# tm8.net
KiCad netlist of a schematic drawn in EAGLE
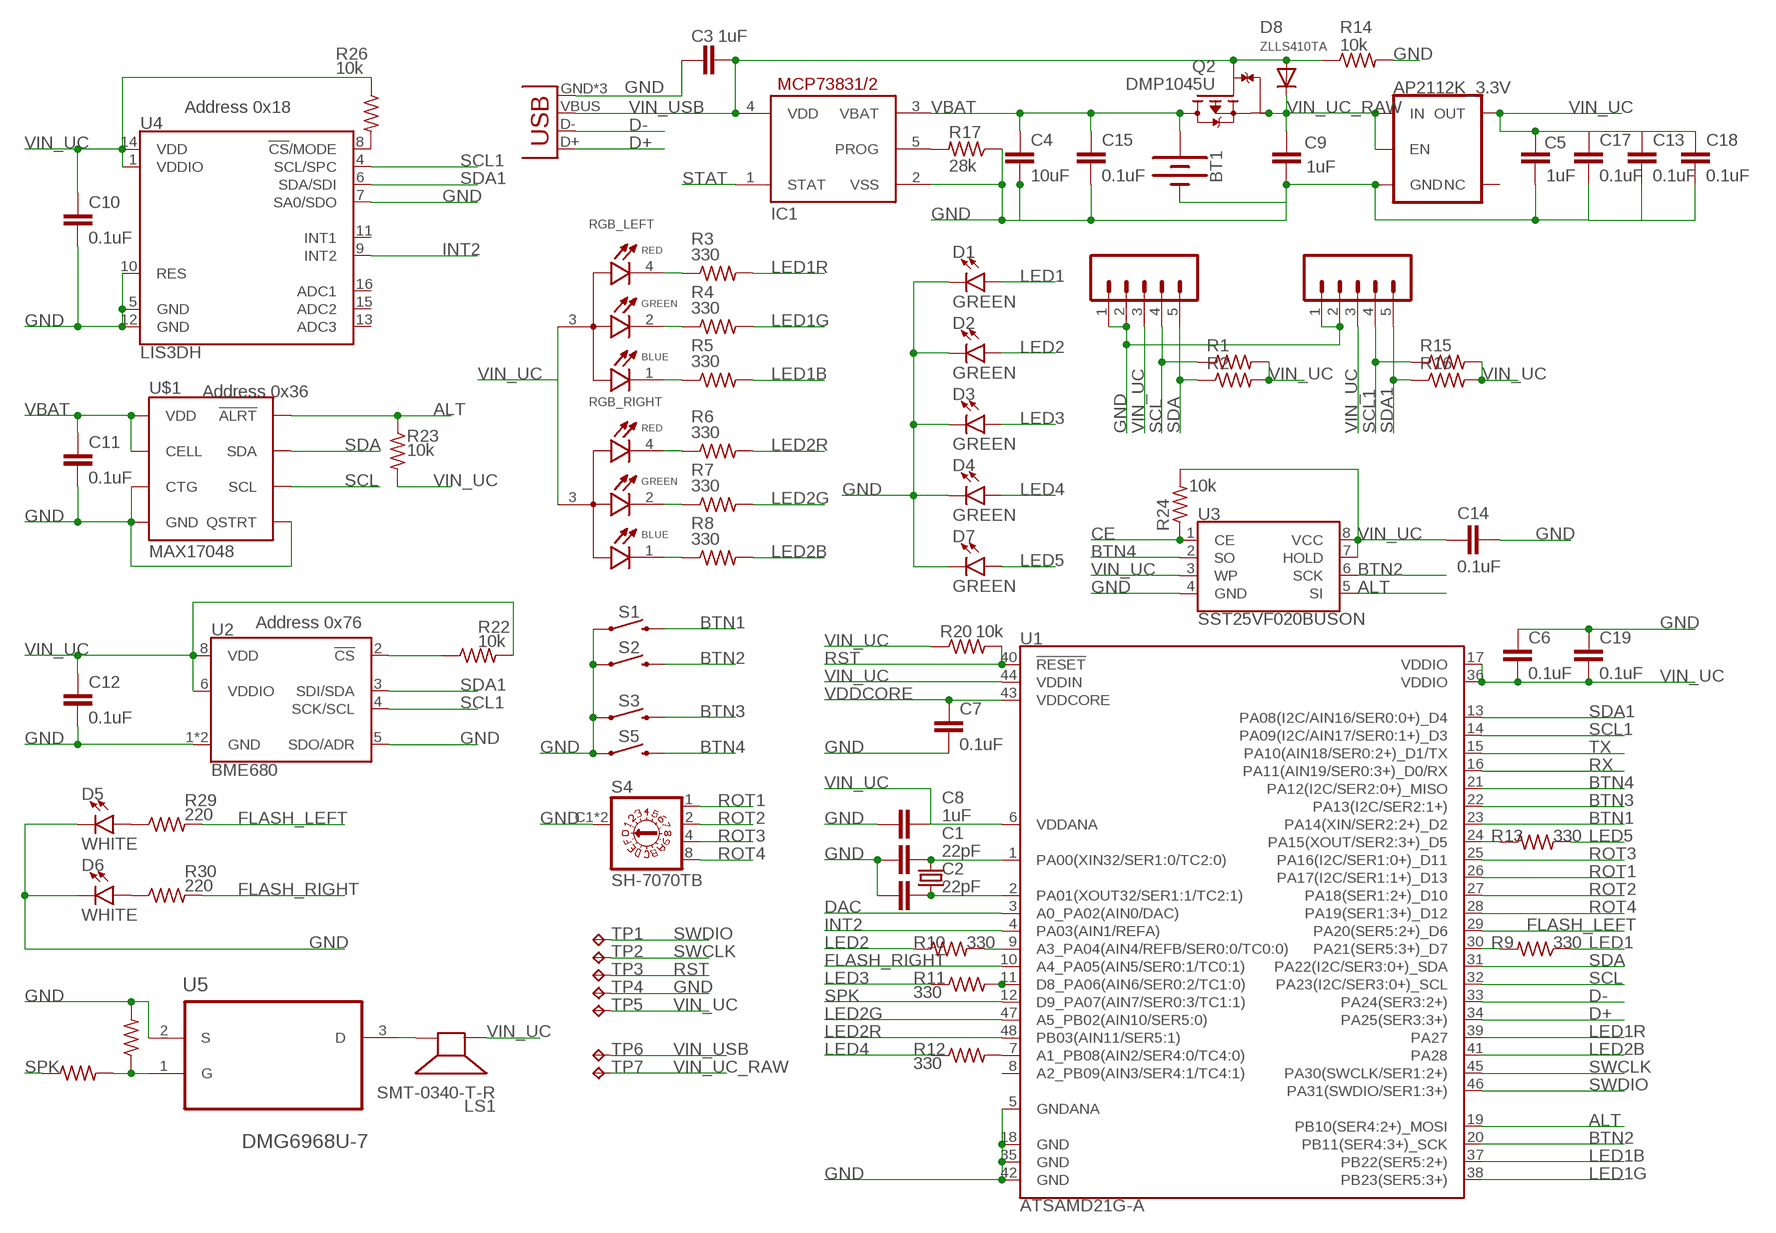
[diagram p0: schematic, sheet 1]

(export (version "E")
  (design (tool "Eeschema 10.0.6"))
  (components
    (comp (ref "AP2112K_3.3V")
      (value "3.3V")
      (footprint "eagle-import:SOT23-5")
      (libsource (lib "eagle-import") (part "V_REG_AP2112K-3.3V"))
    )
    (comp (ref "BT1")
      (value "BATTERY-20MM_SMD_4LEGS_OVERPASTE_INNER")
      (footprint "eagle-import:BATTCON_20MM_4LEGS_OVERPASTE_INNER")
      (libsource (lib "eagle-import") (part "BATTERY-20MM_SMD_4LEGS_OVERPASTE_INNER"))
    )
    (comp (ref "C1")
      (value "22pF")
      (footprint "eagle-import:C0402")
      (libsource (lib "eagle-import") (part "C-EUC0402"))
    )
    (comp (ref "C2")
      (value "22pF")
      (footprint "eagle-import:C0402")
      (libsource (lib "eagle-import") (part "C-EUC0402"))
    )
    (comp (ref "C3")
      (value "1uF")
      (footprint "eagle-import:C0402")
      (libsource (lib "eagle-import") (part "C-EUC0402"))
    )
    (comp (ref "C4")
      (value "10uF")
      (footprint "eagle-import:C0402")
      (libsource (lib "eagle-import") (part "C-EUC0402"))
    )
    (comp (ref "C5")
      (value "1uF")
      (footprint "eagle-import:C0402")
      (libsource (lib "eagle-import") (part "C-EUC0402"))
    )
    (comp (ref "C6")
      (value "0.1uF")
      (footprint "eagle-import:C0402")
      (libsource (lib "eagle-import") (part "C-EUC0402"))
    )
    (comp (ref "C7")
      (value "0.1uF")
      (footprint "eagle-import:C0402")
      (libsource (lib "eagle-import") (part "C-EUC0402"))
    )
    (comp (ref "C8")
      (value "1uF")
      (footprint "eagle-import:C0402")
      (libsource (lib "eagle-import") (part "C-EUC0402"))
    )
    (comp (ref "C9")
      (value "1uF")
      (footprint "eagle-import:C0402")
      (libsource (lib "eagle-import") (part "C-EUC0402"))
    )
    (comp (ref "C10")
      (value "0.1uF")
      (footprint "eagle-import:C0402")
      (libsource (lib "eagle-import") (part "C-EUC0402"))
    )
    (comp (ref "C11")
      (value "0.1uF")
      (footprint "eagle-import:C0402")
      (libsource (lib "eagle-import") (part "C-EUC0402"))
    )
    (comp (ref "C12")
      (value "0.1uF")
      (footprint "eagle-import:C0402")
      (libsource (lib "eagle-import") (part "C-EUC0402"))
    )
    (comp (ref "C13")
      (value "0.1uF")
      (footprint "eagle-import:C0402")
      (libsource (lib "eagle-import") (part "C-EUC0402"))
    )
    (comp (ref "C14")
      (value "0.1uF")
      (footprint "eagle-import:C0402")
      (libsource (lib "eagle-import") (part "C-EUC0402"))
    )
    (comp (ref "C15")
      (value "0.1uF")
      (footprint "eagle-import:C0402")
      (libsource (lib "eagle-import") (part "C-EUC0402"))
    )
    (comp (ref "C17")
      (value "0.1uF")
      (footprint "eagle-import:C0402")
      (libsource (lib "eagle-import") (part "C-EUC0402"))
    )
    (comp (ref "C18")
      (value "0.1uF")
      (footprint "eagle-import:C0402")
      (libsource (lib "eagle-import") (part "C-EUC0402"))
    )
    (comp (ref "C19")
      (value "0.1uF")
      (footprint "eagle-import:C0402")
      (libsource (lib "eagle-import") (part "C-EUC0402"))
    )
    (comp (ref "D1")
      (value "GREEN")
      (footprint "eagle-import:LED-1206")
      (libsource (lib "eagle-import") (part "LED-GREEN1206"))
    )
    (comp (ref "D2")
      (value "GREEN")
      (footprint "eagle-import:LED-1206")
      (libsource (lib "eagle-import") (part "LED-GREEN1206"))
    )
    (comp (ref "D3")
      (value "GREEN")
      (footprint "eagle-import:LED-1206")
      (libsource (lib "eagle-import") (part "LED-GREEN1206"))
    )
    (comp (ref "D4")
      (value "GREEN")
      (footprint "eagle-import:LED-1206")
      (libsource (lib "eagle-import") (part "LED-GREEN1206"))
    )
    (comp (ref "D5")
      (value "WHITE")
      (footprint "eagle-import:LED-1206")
      (libsource (lib "eagle-import") (part "LED-WHITE1206"))
    )
    (comp (ref "D6")
      (value "WHITE")
      (footprint "eagle-import:LED-1206")
      (libsource (lib "eagle-import") (part "LED-WHITE1206"))
    )
    (comp (ref "D7")
      (value "GREEN")
      (footprint "eagle-import:LED-1206")
      (libsource (lib "eagle-import") (part "LED-GREEN1206"))
    )
    (comp (ref "D8")
      (value "ZLLS410TA")
      (footprint "eagle-import:SOD-323F")
      (libsource (lib "eagle-import") (part "DIODESOD-323F"))
    )
    (comp (ref "IC1")
      (value "MCP73831/OT")
      (footprint "eagle-import:SOT23-5L")
      (libsource (lib "eagle-import") (part "MCP73831/OT"))
    )
    (comp (ref "JP2")
      (value "USB-MICROB")
      (footprint "eagle-import:USB-MICROB")
      (libsource (lib "eagle-import") (part "USB-MICROB"))
    )
    (comp (ref "LCD1")
      (value "CONN_05VERT_FEMALE_HEADER")
      (footprint "eagle-import:1X05_SMD_VERTICAL_COMBO")
      (libsource (lib "eagle-import") (part "CONN_05VERT_FEMALE_HEADER"))
    )
    (comp (ref "LCD2")
      (value "CONN_05VERT_FEMALE_HEADER")
      (footprint "eagle-import:1X05_SMD_VERTICAL_COMBO")
      (libsource (lib "eagle-import") (part "CONN_05VERT_FEMALE_HEADER"))
    )
    (comp (ref "LS1")
      (value "SMT-0340-T-R")
      (footprint "eagle-import:XDCR_SMT-0340-T-R")
      (fields (field (name "MANUFACTURER") "Pui Audio"))
      (libsource (lib "eagle-import") (part "SMT-0340-T-R"))
    )
    (comp (ref "Q2")
      (value "DMP1045U")
      (footprint "eagle-import:SOT91P240X110-3N")
      (fields (field (name "MF") "Diodes Inc."))
      (libsource (lib "eagle-import") (part "DMP1045U"))
    )
    (comp (ref "R1")
      (value "R-US_R0402")
      (footprint "eagle-import:R0402")
      (libsource (lib "eagle-import") (part "adafruit_25768682_R-US_R0402"))
    )
    (comp (ref "R2")
      (value "R-US_R0402")
      (footprint "eagle-import:R0402")
      (libsource (lib "eagle-import") (part "adafruit_25768682_R-US_R0402"))
    )
    (comp (ref "R3")
      (value "330")
      (footprint "eagle-import:R0402")
      (libsource (lib "eagle-import") (part "rcl_334_R-US_R0402"))
    )
    (comp (ref "R4")
      (value "330")
      (footprint "eagle-import:R0402")
      (libsource (lib "eagle-import") (part "rcl_334_R-US_R0402"))
    )
    (comp (ref "R5")
      (value "330")
      (footprint "eagle-import:R0402")
      (libsource (lib "eagle-import") (part "rcl_334_R-US_R0402"))
    )
    (comp (ref "R6")
      (value "330")
      (footprint "eagle-import:R0402")
      (libsource (lib "eagle-import") (part "rcl_334_R-US_R0402"))
    )
    (comp (ref "R7")
      (value "330")
      (footprint "eagle-import:R0402")
      (libsource (lib "eagle-import") (part "rcl_334_R-US_R0402"))
    )
    (comp (ref "R8")
      (value "330")
      (footprint "eagle-import:R0402")
      (libsource (lib "eagle-import") (part "rcl_334_R-US_R0402"))
    )
    (comp (ref "R9")
      (value "330")
      (footprint "eagle-import:R0402")
      (libsource (lib "eagle-import") (part "rcl_334_R-US_R0402"))
    )
    (comp (ref "R10")
      (value "330")
      (footprint "eagle-import:R0402")
      (libsource (lib "eagle-import") (part "rcl_334_R-US_R0402"))
    )
    (comp (ref "R11")
      (value "330")
      (footprint "eagle-import:R0402")
      (libsource (lib "eagle-import") (part "rcl_334_R-US_R0402"))
    )
    (comp (ref "R12")
      (value "330")
      (footprint "eagle-import:R0402")
      (libsource (lib "eagle-import") (part "rcl_334_R-US_R0402"))
    )
    (comp (ref "R13")
      (value "330")
      (footprint "eagle-import:R0402")
      (libsource (lib "eagle-import") (part "rcl_334_R-US_R0402"))
    )
    (comp (ref "R14")
      (value "10k")
      (footprint "eagle-import:R0402")
      (libsource (lib "eagle-import") (part "R-US_R0402"))
    )
    (comp (ref "R15")
      (value "R-US_R0402")
      (footprint "eagle-import:R0402")
      (libsource (lib "eagle-import") (part "adafruit_25768682_R-US_R0402"))
    )
    (comp (ref "R16")
      (value "R-US_R0402")
      (footprint "eagle-import:R0402")
      (libsource (lib "eagle-import") (part "adafruit_25768682_R-US_R0402"))
    )
    (comp (ref "R17")
      (value "28k")
      (footprint "eagle-import:R0402")
      (libsource (lib "eagle-import") (part "adafruit_25768682_R-US_R0402"))
    )
    (comp (ref "R18")
      (value "220")
      (footprint "eagle-import:R0402")
      (libsource (lib "eagle-import") (part "rcl_334_R-US_R0402"))
    )
    (comp (ref "R19")
      (value "220")
      (footprint "eagle-import:R0402")
      (libsource (lib "eagle-import") (part "rcl_334_R-US_R0402"))
    )
    (comp (ref "R20")
      (value "10k")
      (footprint "eagle-import:R0402")
      (libsource (lib "eagle-import") (part "adafruit_25768682_R-US_R0402"))
    )
    (comp (ref "R22")
      (value "10k")
      (footprint "eagle-import:R0402")
      (libsource (lib "eagle-import") (part "rcl_334_R-US_R0402"))
    )
    (comp (ref "R23")
      (value "10k")
      (footprint "eagle-import:R0402")
      (libsource (lib "eagle-import") (part "rcl_334_R-US_R0402"))
    )
    (comp (ref "R24")
      (value "10k")
      (footprint "eagle-import:R0402")
      (libsource (lib "eagle-import") (part "rcl_334_R-US_R0402"))
    )
    (comp (ref "R26")
      (value "10k")
      (footprint "eagle-import:R0402")
      (libsource (lib "eagle-import") (part "rcl_334_R-US_R0402"))
    )
    (comp (ref "R29")
      (value "220")
      (footprint "eagle-import:R0402")
      (libsource (lib "eagle-import") (part "rcl_334_R-US_R0402"))
    )
    (comp (ref "R30")
      (value "220")
      (footprint "eagle-import:R0402")
      (libsource (lib "eagle-import") (part "rcl_334_R-US_R0402"))
    )
    (comp (ref "RGB_LEFT")
      (value "EAST1616RGBA3")
      (footprint "eagle-import:LED_EAST1616RGBA3")
      (fields (field (name "MF") "Everlight Electronics"))
      (libsource (lib "eagle-import") (part "EAST1616RGBA3"))
    )
    (comp (ref "RGB_RIGHT")
      (value "EAST1616RGBA3")
      (footprint "eagle-import:LED_EAST1616RGBA3")
      (fields (field (name "MF") "Everlight Electronics"))
      (libsource (lib "eagle-import") (part "EAST1616RGBA3"))
    )
    (comp (ref "S1")
      (value "MOMENTARY-SWITCH-SPST-SMD-6.0X3.5MM")
      (footprint "eagle-import:TACTILE_SWITCH_SMD_6.0X3.5MM")
      (libsource (lib "eagle-import") (part "MOMENTARY-SWITCH-SPST-SMD-6.0X3.5MM"))
    )
    (comp (ref "S2")
      (value "MOMENTARY-SWITCH-SPST-SMD-6.0X3.5MM")
      (footprint "eagle-import:TACTILE_SWITCH_SMD_6.0X3.5MM")
      (libsource (lib "eagle-import") (part "MOMENTARY-SWITCH-SPST-SMD-6.0X3.5MM"))
    )
    (comp (ref "S3")
      (value "MOMENTARY-SWITCH-SPST-SMD-6.0X3.5MM")
      (footprint "eagle-import:TACTILE_SWITCH_SMD_6.0X3.5MM")
      (libsource (lib "eagle-import") (part "MOMENTARY-SWITCH-SPST-SMD-6.0X3.5MM"))
    )
    (comp (ref "S4")
      (value "SH-7070TB")
      (footprint "eagle-import:SH-7070B")
      (fields (field (name "MF") "Nidec Copal"))
      (libsource (lib "eagle-import") (part "SH-7070TB"))
    )
    (comp (ref "S5")
      (value "MOMENTARY-SWITCH-SPST-SMD-6.0X3.5MM")
      (footprint "eagle-import:TACTILE_SWITCH_SMD_6.0X3.5MM")
      (libsource (lib "eagle-import") (part "MOMENTARY-SWITCH-SPST-SMD-6.0X3.5MM"))
    )
    (comp (ref "TP1")
      (value "TPTP14R")
      (footprint "eagle-import:TP14R")
      (libsource (lib "eagle-import") (part "TPTP14R"))
    )
    (comp (ref "TP2")
      (value "TPTP14R")
      (footprint "eagle-import:TP14R")
      (libsource (lib "eagle-import") (part "TPTP14R"))
    )
    (comp (ref "TP3")
      (value "TPTP14R")
      (footprint "eagle-import:TP14R")
      (libsource (lib "eagle-import") (part "TPTP14R"))
    )
    (comp (ref "TP4")
      (value "TPTP14R")
      (footprint "eagle-import:TP14R")
      (libsource (lib "eagle-import") (part "TPTP14R"))
    )
    (comp (ref "TP5")
      (value "TPTP14R")
      (footprint "eagle-import:TP14R")
      (libsource (lib "eagle-import") (part "TPTP14R"))
    )
    (comp (ref "TP6")
      (value "TPTP14R")
      (footprint "eagle-import:TP14R")
      (libsource (lib "eagle-import") (part "TPTP14R"))
    )
    (comp (ref "TP7")
      (value "TPTP14R")
      (footprint "eagle-import:TP14R")
      (libsource (lib "eagle-import") (part "TPTP14R"))
    )
    (comp (ref "U$1")
      (value "MAX17048")
      (footprint "eagle-import:DFN-8")
      (libsource (lib "eagle-import") (part "MAX17048DFN8"))
    )
    (comp (ref "U1")
      (value "ATSAMD21G-A")
      (footprint "eagle-import:TQFP-48")
      (libsource (lib "eagle-import") (part "ATSAMD21G-A"))
    )
    (comp (ref "U2")
      (value "BME680")
      (footprint "eagle-import:LGA3.0X3.0")
      (libsource (lib "eagle-import") (part "BME680-LGA"))
    )
    (comp (ref "U3")
      (value "SST25VF020BUSON")
      (footprint "eagle-import:USON_3X2MM")
      (fields
        (field (name "DIGIKEY_PART") "SST25VF020B-80-4I-Q3AE-TCT-ND")
        (field (name "MANU_PART") "SST25VF020B-80-4I-Q3AE-T")
      )
      (libsource (lib "eagle-import") (part "SST25VF020BUSON"))
    )
    (comp (ref "U4")
      (value "LIS3DH")
      (footprint "eagle-import:LGA-16-3X3")
      (libsource (lib "eagle-import") (part "LIS3DH"))
    )
    (comp (ref "U5")
      (value "DMG6968U-7")
      (footprint "eagle-import:SOT95P240X110-3N")
      (fields (field (name "MF") "Diodes Inc."))
      (libsource (lib "eagle-import") (part "DMG6968U-7"))
    )
    (comp (ref "Y1")
      (value "32.768kHz")
      (footprint "eagle-import:CRYSTAL-SMD-3.2X1.5MM")
      (libsource (lib "eagle-import") (part "CRYSTAL-32.768KHZSMD-3.2X1.5"))
    )
  )
  (nets
    (net (code "1") (name "/ALT") (class "Default")
      (node (ref "R23") (pin "1") (pinfunction "1_1") (pintype "passive"))
      (node (ref "U$1") (pin "P$5") (pinfunction "~{ALRT}_P$5") (pintype "bidirectional"))
      (node (ref "U1") (pin "19") (pinfunction "PB10(SER4:2+)_MOSI_19") (pintype "bidirectional"))
      (node (ref "U3") (pin "5") (pinfunction "SI_5") (pintype "bidirectional"))
    )
    (net (code "2") (name "/BTN1") (class "Default")
      (node (ref "S1") (pin "2") (pinfunction "2_2") (pintype "passive"))
      (node (ref "U1") (pin "23") (pinfunction "PA14(XIN/SER2:2+)_D2_23") (pintype "bidirectional"))
    )
    (net (code "3") (name "/BTN2") (class "Default")
      (node (ref "S2") (pin "2") (pinfunction "2_2") (pintype "passive"))
      (node (ref "U1") (pin "20") (pinfunction "PB11(SER4:3+)_SCK_20") (pintype "bidirectional"))
      (node (ref "U3") (pin "6") (pinfunction "SCK_6") (pintype "bidirectional"))
    )
    (net (code "4") (name "/BTN3") (class "Default")
      (node (ref "S3") (pin "2") (pinfunction "2_2") (pintype "passive"))
      (node (ref "U1") (pin "22") (pinfunction "PA13(I2C/SER2:1+)_22") (pintype "bidirectional"))
    )
    (net (code "5") (name "/BTN4") (class "Default")
      (node (ref "S5") (pin "2") (pinfunction "2_2") (pintype "passive"))
      (node (ref "U1") (pin "21") (pinfunction "PA12(I2C/SER2:0+)_MISO_21") (pintype "bidirectional"))
      (node (ref "U3") (pin "2") (pinfunction "SO_2") (pintype "bidirectional"))
    )
    (net (code "6") (name "/CE") (class "Default")
      (node (ref "R24") (pin "1") (pinfunction "1_1") (pintype "passive"))
      (node (ref "U3") (pin "1") (pinfunction "CE_1") (pintype "bidirectional"))
    )
    (net (code "7") (name "/D+") (class "Default")
      (node (ref "JP2") (pin "D+") (pinfunction "D+_D+") (pintype "bidirectional"))
      (node (ref "U1") (pin "34") (pinfunction "PA25(SER3:3+)_34") (pintype "bidirectional"))
    )
    (net (code "8") (name "/D-") (class "Default")
      (node (ref "JP2") (pin "D-") (pinfunction "D-_D-") (pintype "bidirectional"))
      (node (ref "U1") (pin "33") (pinfunction "PA24(SER3:2+)_33") (pintype "bidirectional"))
    )
    (net (code "9") (name "/DAC") (class "Default")
      (node (ref "U1") (pin "3") (pinfunction "A0_PA02(AIN0/DAC)_3") (pintype "bidirectional"))
    )
    (net (code "10") (name "/FLASH_LEFT") (class "Default")
      (node (ref "R29") (pin "2") (pinfunction "2_2") (pintype "passive"))
      (node (ref "U1") (pin "29") (pinfunction "PA20(SER5:2+)_D6_29") (pintype "bidirectional"))
    )
    (net (code "11") (name "/FLASH_RIGHT") (class "Default")
      (node (ref "R30") (pin "2") (pinfunction "2_2") (pintype "passive"))
      (node (ref "U1") (pin "10") (pinfunction "A4_PA05(AIN5/SER0:1/TC0:1)_10") (pintype "bidirectional"))
    )
    (net (code "12") (name "/GND") (class "Default")
      (node (ref "AP2112K_3.3V") (pin "2") (pinfunction "GND_2") (pintype "input"))
      (node (ref "BT1") (pin "2") (pinfunction "-_2") (pintype "power_in"))
      (node (ref "C1") (pin "1") (pinfunction "1_1") (pintype "passive"))
      (node (ref "C10") (pin "2") (pinfunction "2_2") (pintype "passive"))
      (node (ref "C11") (pin "2") (pinfunction "2_2") (pintype "passive"))
      (node (ref "C12") (pin "2") (pinfunction "2_2") (pintype "passive"))
      (node (ref "C13") (pin "2") (pinfunction "2_2") (pintype "passive"))
      (node (ref "C14") (pin "2") (pinfunction "2_2") (pintype "passive"))
      (node (ref "C15") (pin "2") (pinfunction "2_2") (pintype "passive"))
      (node (ref "C17") (pin "2") (pinfunction "2_2") (pintype "passive"))
      (node (ref "C18") (pin "2") (pinfunction "2_2") (pintype "passive"))
      (node (ref "C19") (pin "1") (pinfunction "1_1") (pintype "passive"))
      (node (ref "C2") (pin "1") (pinfunction "1_1") (pintype "passive"))
      (node (ref "C3") (pin "1") (pinfunction "1_1") (pintype "passive"))
      (node (ref "C4") (pin "2") (pinfunction "2_2") (pintype "passive"))
      (node (ref "C5") (pin "2") (pinfunction "2_2") (pintype "passive"))
      (node (ref "C6") (pin "1") (pinfunction "1_1") (pintype "passive"))
      (node (ref "C7") (pin "2") (pinfunction "2_2") (pintype "passive"))
      (node (ref "C8") (pin "1") (pinfunction "1_1") (pintype "passive"))
      (node (ref "C9") (pin "2") (pinfunction "2_2") (pintype "passive"))
      (node (ref "D1") (pin "C") (pinfunction "C_C") (pintype "passive"))
      (node (ref "D2") (pin "C") (pinfunction "C_C") (pintype "passive"))
      (node (ref "D3") (pin "C") (pinfunction "C_C") (pintype "passive"))
      (node (ref "D4") (pin "C") (pinfunction "C_C") (pintype "passive"))
      (node (ref "D5") (pin "C") (pinfunction "C_C") (pintype "passive"))
      (node (ref "D6") (pin "C") (pinfunction "C_C") (pintype "passive"))
      (node (ref "D7") (pin "C") (pinfunction "C_C") (pintype "passive"))
      (node (ref "IC1") (pin "2") (pinfunction "VSS_2") (pintype "power_in"))
      (node (ref "JP2") (pin "GND") (pinfunction "GND_GND") (pintype "bidirectional"))
      (node (ref "JP2") (pin "MT1") (pinfunction "GND_MT1") (pintype "bidirectional"))
      (node (ref "JP2") (pin "MT2") (pinfunction "GND_MT2") (pintype "bidirectional"))
      (node (ref "LCD1") (pin "1") (pinfunction "1_1") (pintype "passive"))
      (node (ref "LCD1") (pin "2") (pinfunction "2_2") (pintype "passive"))
      (node (ref "LCD2") (pin "1") (pinfunction "1_1") (pintype "passive"))
      (node (ref "LCD2") (pin "2") (pinfunction "2_2") (pintype "passive"))
      (node (ref "R14") (pin "2") (pinfunction "2_2") (pintype "passive"))
      (node (ref "R17") (pin "1") (pinfunction "1_1") (pintype "passive"))
      (node (ref "R19") (pin "2") (pinfunction "2_2") (pintype "passive"))
      (node (ref "S1") (pin "1") (pinfunction "1_1") (pintype "passive"))
      (node (ref "S2") (pin "1") (pinfunction "1_1") (pintype "passive"))
      (node (ref "S3") (pin "1") (pinfunction "1_1") (pintype "passive"))
      (node (ref "S4") (pin "C1") (pinfunction "C_C1") (pintype "passive"))
      (node (ref "S4") (pin "C2") (pinfunction "C_C2") (pintype "passive"))
      (node (ref "S5") (pin "1") (pinfunction "1_1") (pintype "passive"))
      (node (ref "TP4") (pin "TP") (pinfunction "TP_TP") (pintype "input"))
      (node (ref "U$1") (pin "P$1") (pinfunction "CTG_P$1") (pintype "input"))
      (node (ref "U$1") (pin "P$4") (pinfunction "GND_P$4") (pintype "bidirectional"))
      (node (ref "U$1") (pin "P$6") (pinfunction "QSTRT_P$6") (pintype "bidirectional"))
      (node (ref "U$1") (pin "P$9") (pinfunction "GND_P$9") (pintype "bidirectional"))
      (node (ref "U1") (pin "18") (pinfunction "GND_18") (pintype "bidirectional"))
      (node (ref "U1") (pin "35") (pinfunction "GND_35") (pintype "bidirectional"))
      (node (ref "U1") (pin "42") (pinfunction "GND_42") (pintype "bidirectional"))
      (node (ref "U1") (pin "5") (pinfunction "GNDANA_5") (pintype "bidirectional"))
      (node (ref "U2") (pin "1") (pinfunction "GND_1") (pintype "bidirectional"))
      (node (ref "U2") (pin "5") (pinfunction "SDO/ADR_5") (pintype "bidirectional"))
      (node (ref "U2") (pin "7") (pinfunction "GND_7") (pintype "bidirectional"))
      (node (ref "U3") (pin "4") (pinfunction "GND_4") (pintype "power_in"))
      (node (ref "U4") (pin "10") (pinfunction "RES_10") (pintype "bidirectional"))
      (node (ref "U4") (pin "12") (pinfunction "GND_12") (pintype "bidirectional"))
      (node (ref "U4") (pin "5") (pinfunction "GND_5") (pintype "bidirectional"))
      (node (ref "U4") (pin "7") (pinfunction "SA0/SDO_7") (pintype "bidirectional"))
      (node (ref "U5") (pin "2") (pinfunction "S_2") (pintype "passive"))
    )
    (net (code "13") (name "/INT2") (class "Default")
      (node (ref "U1") (pin "4") (pinfunction "PA03(AIN1/REFA)_4") (pintype "bidirectional"))
      (node (ref "U4") (pin "9") (pinfunction "INT2_9") (pintype "bidirectional"))
    )
    (net (code "14") (name "/LED1") (class "Default")
      (node (ref "D1") (pin "A") (pinfunction "A_A") (pintype "passive"))
      (node (ref "R9") (pin "1") (pinfunction "1_1") (pintype "passive"))
    )
    (net (code "15") (name "/LED1B") (class "Default")
      (node (ref "R5") (pin "2") (pinfunction "2_2") (pintype "passive"))
      (node (ref "U1") (pin "37") (pinfunction "PB22(SER5:2+)_37") (pintype "bidirectional"))
    )
    (net (code "16") (name "/LED1G") (class "Default")
      (node (ref "R4") (pin "2") (pinfunction "2_2") (pintype "passive"))
      (node (ref "U1") (pin "38") (pinfunction "PB23(SER5:3+)_38") (pintype "bidirectional"))
    )
    (net (code "17") (name "/LED1R") (class "Default")
      (node (ref "R3") (pin "2") (pinfunction "2_2") (pintype "passive"))
      (node (ref "U1") (pin "39") (pinfunction "PA27_39") (pintype "bidirectional"))
    )
    (net (code "18") (name "/LED2") (class "Default")
      (node (ref "D2") (pin "A") (pinfunction "A_A") (pintype "passive"))
      (node (ref "R10") (pin "1") (pinfunction "1_1") (pintype "passive"))
    )
    (net (code "19") (name "/LED2B") (class "Default")
      (node (ref "R8") (pin "2") (pinfunction "2_2") (pintype "passive"))
      (node (ref "U1") (pin "41") (pinfunction "PA28_41") (pintype "bidirectional"))
    )
    (net (code "20") (name "/LED2G") (class "Default")
      (node (ref "R7") (pin "2") (pinfunction "2_2") (pintype "passive"))
      (node (ref "U1") (pin "47") (pinfunction "A5_PB02(AIN10/SER5:0)_47") (pintype "bidirectional"))
    )
    (net (code "21") (name "/LED2R") (class "Default")
      (node (ref "R6") (pin "2") (pinfunction "2_2") (pintype "passive"))
      (node (ref "U1") (pin "48") (pinfunction "PB03(AIN11/SER5:1)_48") (pintype "bidirectional"))
    )
    (net (code "22") (name "/LED3") (class "Default")
      (node (ref "D3") (pin "A") (pinfunction "A_A") (pintype "passive"))
      (node (ref "R11") (pin "1") (pinfunction "1_1") (pintype "passive"))
    )
    (net (code "23") (name "/LED4") (class "Default")
      (node (ref "D4") (pin "A") (pinfunction "A_A") (pintype "passive"))
      (node (ref "R12") (pin "1") (pinfunction "1_1") (pintype "passive"))
    )
    (net (code "24") (name "/LED5") (class "Default")
      (node (ref "D7") (pin "A") (pinfunction "A_A") (pintype "passive"))
      (node (ref "R13") (pin "2") (pinfunction "2_2") (pintype "passive"))
    )
    (net (code "25") (name "/ROT1") (class "Default")
      (node (ref "S4") (pin "1") (pinfunction "1_1") (pintype "passive"))
      (node (ref "U1") (pin "26") (pinfunction "PA17(I2C/SER1:1+)_D13_26") (pintype "bidirectional"))
    )
    (net (code "26") (name "/ROT2") (class "Default")
      (node (ref "S4") (pin "2") (pinfunction "2_2") (pintype "passive"))
      (node (ref "U1") (pin "27") (pinfunction "PA18(SER1:2+)_D10_27") (pintype "bidirectional"))
    )
    (net (code "27") (name "/ROT3") (class "Default")
      (node (ref "S4") (pin "4") (pinfunction "4_4") (pintype "passive"))
      (node (ref "U1") (pin "25") (pinfunction "PA16(I2C/SER1:0+)_D11_25") (pintype "bidirectional"))
    )
    (net (code "28") (name "/ROT4") (class "Default")
      (node (ref "S4") (pin "8") (pinfunction "8_8") (pintype "passive"))
      (node (ref "U1") (pin "28") (pinfunction "PA19(SER1:3+)_D12_28") (pintype "bidirectional"))
    )
    (net (code "29") (name "/RST") (class "Default")
      (node (ref "R20") (pin "2") (pinfunction "2_2") (pintype "passive"))
      (node (ref "TP3") (pin "TP") (pinfunction "TP_TP") (pintype "input"))
      (node (ref "U1") (pin "40") (pinfunction "~{RESET}_40") (pintype "bidirectional"))
    )
    (net (code "30") (name "/RX") (class "Default")
      (node (ref "U1") (pin "16") (pinfunction "PA11(AIN19/SER0:3+)_D0/RX_16") (pintype "bidirectional"))
    )
    (net (code "31") (name "/SCL") (class "Default")
      (node (ref "LCD1") (pin "4") (pinfunction "4_4") (pintype "passive"))
      (node (ref "R1") (pin "1") (pinfunction "1_1") (pintype "passive"))
      (node (ref "U$1") (pin "P$7") (pinfunction "SCL_P$7") (pintype "output"))
      (node (ref "U1") (pin "32") (pinfunction "PA23(I2C/SER3:0+)_SCL_32") (pintype "bidirectional"))
    )
    (net (code "32") (name "/SCL1") (class "Default")
      (node (ref "LCD2") (pin "4") (pinfunction "4_4") (pintype "passive"))
      (node (ref "R15") (pin "1") (pinfunction "1_1") (pintype "passive"))
      (node (ref "U1") (pin "14") (pinfunction "PA09(I2C/AIN17/SER0:1+)_D3_14") (pintype "bidirectional"))
      (node (ref "U2") (pin "4") (pinfunction "SCK/SCL_4") (pintype "bidirectional"))
      (node (ref "U4") (pin "4") (pinfunction "SCL/SPC_4") (pintype "bidirectional"))
    )
    (net (code "33") (name "/SDA") (class "Default")
      (node (ref "LCD1") (pin "5") (pinfunction "5_5") (pintype "passive"))
      (node (ref "R2") (pin "1") (pinfunction "1_1") (pintype "passive"))
      (node (ref "U$1") (pin "P$8") (pinfunction "SDA_P$8") (pintype "input"))
      (node (ref "U1") (pin "31") (pinfunction "PA22(I2C/SER3:0+)_SDA_31") (pintype "bidirectional"))
    )
    (net (code "34") (name "/SDA1") (class "Default")
      (node (ref "LCD2") (pin "5") (pinfunction "5_5") (pintype "passive"))
      (node (ref "R16") (pin "1") (pinfunction "1_1") (pintype "passive"))
      (node (ref "U1") (pin "13") (pinfunction "PA08(I2C/AIN16/SER0:0+)_D4_13") (pintype "bidirectional"))
      (node (ref "U2") (pin "3") (pinfunction "SDI/SDA_3") (pintype "bidirectional"))
      (node (ref "U4") (pin "6") (pinfunction "SDA/SDI_6") (pintype "bidirectional"))
    )
    (net (code "35") (name "/SPK") (class "Default")
      (node (ref "R18") (pin "1") (pinfunction "1_1") (pintype "passive"))
      (node (ref "U1") (pin "12") (pinfunction "D9_PA07(AIN7/SER0:3/TC1:1)_12") (pintype "bidirectional"))
    )
    (net (code "36") (name "/STAT") (class "Default")
      (node (ref "IC1") (pin "1") (pinfunction "STAT_1") (pintype "output"))
    )
    (net (code "37") (name "/SWCLK") (class "Default")
      (node (ref "TP2") (pin "TP") (pinfunction "TP_TP") (pintype "input"))
      (node (ref "U1") (pin "45") (pinfunction "PA30(SWCLK/SER1:2+)_45") (pintype "bidirectional"))
    )
    (net (code "38") (name "/SWDIO") (class "Default")
      (node (ref "TP1") (pin "TP") (pinfunction "TP_TP") (pintype "input"))
      (node (ref "U1") (pin "46") (pinfunction "PA31(SWDIO/SER1:3+)_46") (pintype "bidirectional"))
    )
    (net (code "39") (name "/TX") (class "Default")
      (node (ref "U1") (pin "15") (pinfunction "PA10(AIN18/SER0:2+)_D1/TX_15") (pintype "bidirectional"))
    )
    (net (code "40") (name "/VBAT") (class "Default")
      (node (ref "BT1") (pin "1") (pinfunction "+_1") (pintype "power_in"))
      (node (ref "C11") (pin "1") (pinfunction "1_1") (pintype "passive"))
      (node (ref "C15") (pin "1") (pinfunction "1_1") (pintype "passive"))
      (node (ref "C4") (pin "1") (pinfunction "1_1") (pintype "passive"))
      (node (ref "IC1") (pin "3") (pinfunction "VBAT_3") (pintype "bidirectional"))
      (node (ref "Q2") (pin "3") (pinfunction "D_3") (pintype "passive"))
      (node (ref "U$1") (pin "P$2") (pinfunction "CELL_P$2") (pintype "input"))
      (node (ref "U$1") (pin "P$3") (pinfunction "VDD_P$3") (pintype "bidirectional"))
    )
    (net (code "41") (name "/VDDCORE") (class "Default")
      (node (ref "C7") (pin "1") (pinfunction "1_1") (pintype "passive"))
      (node (ref "U1") (pin "43") (pinfunction "VDDCORE_43") (pintype "bidirectional"))
    )
    (net (code "42") (name "/VIN_UC") (class "Default")
      (node (ref "AP2112K_3.3V") (pin "5") (pinfunction "OUT_5") (pintype "passive"))
      (node (ref "C10") (pin "1") (pinfunction "1_1") (pintype "passive"))
      (node (ref "C12") (pin "1") (pinfunction "1_1") (pintype "passive"))
      (node (ref "C13") (pin "1") (pinfunction "1_1") (pintype "passive"))
      (node (ref "C14") (pin "1") (pinfunction "1_1") (pintype "passive"))
      (node (ref "C17") (pin "1") (pinfunction "1_1") (pintype "passive"))
      (node (ref "C18") (pin "1") (pinfunction "1_1") (pintype "passive"))
      (node (ref "C19") (pin "2") (pinfunction "2_2") (pintype "passive"))
      (node (ref "C5") (pin "1") (pinfunction "1_1") (pintype "passive"))
      (node (ref "C6") (pin "2") (pinfunction "2_2") (pintype "passive"))
      (node (ref "C8") (pin "2") (pinfunction "2_2") (pintype "passive"))
      (node (ref "LCD1") (pin "3") (pinfunction "3_3") (pintype "passive"))
      (node (ref "LCD2") (pin "3") (pinfunction "3_3") (pintype "passive"))
      (node (ref "LS1") (pin "P") (pinfunction "P_P") (pintype "passive"))
      (node (ref "R1") (pin "2") (pinfunction "2_2") (pintype "passive"))
      (node (ref "R15") (pin "2") (pinfunction "2_2") (pintype "passive"))
      (node (ref "R16") (pin "2") (pinfunction "2_2") (pintype "passive"))
      (node (ref "R2") (pin "2") (pinfunction "2_2") (pintype "passive"))
      (node (ref "R20") (pin "1") (pinfunction "1_1") (pintype "passive"))
      (node (ref "R22") (pin "2") (pinfunction "2_2") (pintype "passive"))
      (node (ref "R23") (pin "2") (pinfunction "2_2") (pintype "passive"))
      (node (ref "R24") (pin "2") (pinfunction "2_2") (pintype "passive"))
      (node (ref "R26") (pin "1") (pinfunction "1_1") (pintype "passive"))
      (node (ref "RGB_LEFT") (pin "3") (pinfunction "A_3") (pintype "passive"))
      (node (ref "RGB_RIGHT") (pin "3") (pinfunction "A_3") (pintype "passive"))
      (node (ref "TP5") (pin "TP") (pinfunction "TP_TP") (pintype "input"))
      (node (ref "U1") (pin "17") (pinfunction "VDDIO_17") (pintype "bidirectional"))
      (node (ref "U1") (pin "36") (pinfunction "VDDIO_36") (pintype "bidirectional"))
      (node (ref "U1") (pin "44") (pinfunction "VDDIN_44") (pintype "bidirectional"))
      (node (ref "U1") (pin "6") (pinfunction "VDDANA_6") (pintype "bidirectional"))
      (node (ref "U2") (pin "6") (pinfunction "VDDIO_6") (pintype "bidirectional"))
      (node (ref "U2") (pin "8") (pinfunction "VDD_8") (pintype "bidirectional"))
      (node (ref "U3") (pin "3") (pinfunction "WP_3") (pintype "bidirectional"))
      (node (ref "U3") (pin "7") (pinfunction "HOLD_7") (pintype "bidirectional"))
      (node (ref "U3") (pin "8") (pinfunction "VCC_8") (pintype "power_in"))
      (node (ref "U4") (pin "1") (pinfunction "VDDIO_1") (pintype "bidirectional"))
      (node (ref "U4") (pin "14") (pinfunction "VDD_14") (pintype "bidirectional"))
    )
    (net (code "43") (name "/VIN_UC_RAW") (class "Default")
      (node (ref "AP2112K_3.3V") (pin "1") (pinfunction "IN_1") (pintype "input"))
      (node (ref "AP2112K_3.3V") (pin "3") (pinfunction "EN_3") (pintype "input"))
      (node (ref "C9") (pin "1") (pinfunction "1_1") (pintype "passive"))
      (node (ref "D8") (pin "C") (pinfunction "C_C") (pintype "passive"))
      (node (ref "Q2") (pin "2") (pinfunction "S_2") (pintype "passive"))
      (node (ref "TP7") (pin "TP") (pinfunction "TP_TP") (pintype "input"))
    )
    (net (code "44") (name "/VIN_USB") (class "Default")
      (node (ref "C3") (pin "2") (pinfunction "2_2") (pintype "passive"))
      (node (ref "D8") (pin "A") (pinfunction "A_A") (pintype "passive"))
      (node (ref "IC1") (pin "4") (pinfunction "VDD_4") (pintype "power_in"))
      (node (ref "JP2") (pin "VBUS") (pinfunction "VBUS_VBUS") (pintype "bidirectional"))
      (node (ref "Q2") (pin "1") (pinfunction "G_1") (pintype "passive"))
      (node (ref "R14") (pin "1") (pinfunction "1_1") (pintype "passive"))
      (node (ref "TP6") (pin "TP") (pinfunction "TP_TP") (pintype "input"))
    )
    (net (code "45") (name "Net-(D5-PadA)") (class "Default")
      (node (ref "D5") (pin "A") (pinfunction "A_A") (pintype "passive"))
      (node (ref "R29") (pin "1") (pinfunction "1_1") (pintype "passive"))
    )
    (net (code "46") (name "Net-(D6-PadA)") (class "Default")
      (node (ref "D6") (pin "A") (pinfunction "A_A") (pintype "passive"))
      (node (ref "R30") (pin "1") (pinfunction "1_1") (pintype "passive"))
    )
    (net (code "47") (name "Net-(IC1-PROG)") (class "Default")
      (node (ref "IC1") (pin "5") (pinfunction "PROG_5") (pintype "input"))
      (node (ref "R17") (pin "2") (pinfunction "2_2") (pintype "passive"))
    )
    (net (code "48") (name "Net-(RGB_LEFT-B_C)") (class "Default")
      (node (ref "R5") (pin "1") (pinfunction "1_1") (pintype "passive"))
      (node (ref "RGB_LEFT") (pin "1") (pinfunction "B_C_1") (pintype "passive"))
    )
    (net (code "49") (name "Net-(RGB_LEFT-G_C)") (class "Default")
      (node (ref "R4") (pin "1") (pinfunction "1_1") (pintype "passive"))
      (node (ref "RGB_LEFT") (pin "2") (pinfunction "G_C_2") (pintype "passive"))
    )
    (net (code "50") (name "Net-(RGB_LEFT-R_C)") (class "Default")
      (node (ref "R3") (pin "1") (pinfunction "1_1") (pintype "passive"))
      (node (ref "RGB_LEFT") (pin "4") (pinfunction "R_C_4") (pintype "passive"))
    )
    (net (code "51") (name "Net-(RGB_RIGHT-B_C)") (class "Default")
      (node (ref "R8") (pin "1") (pinfunction "1_1") (pintype "passive"))
      (node (ref "RGB_RIGHT") (pin "1") (pinfunction "B_C_1") (pintype "passive"))
    )
    (net (code "52") (name "Net-(RGB_RIGHT-G_C)") (class "Default")
      (node (ref "R7") (pin "1") (pinfunction "1_1") (pintype "passive"))
      (node (ref "RGB_RIGHT") (pin "2") (pinfunction "G_C_2") (pintype "passive"))
    )
    (net (code "53") (name "Net-(RGB_RIGHT-R_C)") (class "Default")
      (node (ref "R6") (pin "1") (pinfunction "1_1") (pintype "passive"))
      (node (ref "RGB_RIGHT") (pin "4") (pinfunction "R_C_4") (pintype "passive"))
    )
    (net (code "54") (name "Net-(U1-A1_PB08(AIN2{slash}SER4:0{slash}TC4:0))") (class "Default")
      (node (ref "R12") (pin "2") (pinfunction "2_2") (pintype "passive"))
      (node (ref "U1") (pin "7") (pinfunction "A1_PB08(AIN2/SER4:0/TC4:0)_7") (pintype "bidirectional"))
    )
    (net (code "55") (name "Net-(U1-A3_PA04(AIN4{slash}REFB{slash}SER0:0{slash}TC0:0))") (class "Default")
      (node (ref "R10") (pin "2") (pinfunction "2_2") (pintype "passive"))
      (node (ref "U1") (pin "9") (pinfunction "A3_PA04(AIN4/REFB/SER0:0/TC0:0)_9") (pintype "bidirectional"))
    )
    (net (code "56") (name "Net-(U1-D8_PA06(AIN6{slash}SER0:2{slash}TC1:0))") (class "Default")
      (node (ref "R11") (pin "2") (pinfunction "2_2") (pintype "passive"))
      (node (ref "U1") (pin "11") (pinfunction "D8_PA06(AIN6/SER0:2/TC1:0)_11") (pintype "bidirectional"))
    )
    (net (code "57") (name "Net-(U1-PA00(XIN32{slash}SER1:0{slash}TC2:0))") (class "Default")
      (node (ref "C1") (pin "2") (pinfunction "2_2") (pintype "passive"))
      (node (ref "U1") (pin "1") (pinfunction "PA00(XIN32/SER1:0/TC2:0)_1") (pintype "bidirectional"))
      (node (ref "Y1") (pin "P$2") (pinfunction "2_P$2") (pintype "passive"))
    )
    (net (code "58") (name "Net-(U1-PA01(XOUT32{slash}SER1:1{slash}TC2:1))") (class "Default")
      (node (ref "C2") (pin "2") (pinfunction "2_2") (pintype "passive"))
      (node (ref "U1") (pin "2") (pinfunction "PA01(XOUT32/SER1:1/TC2:1)_2") (pintype "bidirectional"))
      (node (ref "Y1") (pin "P$1") (pinfunction "1_P$1") (pintype "passive"))
    )
    (net (code "59") (name "Net-(U1-PA15(XOUT{slash}SER2:3+)_D5)") (class "Default")
      (node (ref "R13") (pin "1") (pinfunction "1_1") (pintype "passive"))
      (node (ref "U1") (pin "24") (pinfunction "PA15(XOUT/SER2:3+)_D5_24") (pintype "bidirectional"))
    )
    (net (code "60") (name "Net-(U1-PA21(SER5:3+)_D7)") (class "Default")
      (node (ref "R9") (pin "2") (pinfunction "2_2") (pintype "passive"))
      (node (ref "U1") (pin "30") (pinfunction "PA21(SER5:3+)_D7_30") (pintype "bidirectional"))
    )
    (net (code "61") (name "Net-(U2-~{CS})") (class "Default")
      (node (ref "R22") (pin "1") (pinfunction "1_1") (pintype "passive"))
      (node (ref "U2") (pin "2") (pinfunction "~{CS}_2") (pintype "bidirectional"))
    )
    (net (code "62") (name "Net-(U4-~{CS}{slash}MODE)") (class "Default")
      (node (ref "R26") (pin "2") (pinfunction "2_2") (pintype "passive"))
      (node (ref "U4") (pin "8") (pinfunction "~{CS}/MODE_8") (pintype "bidirectional"))
    )
    (net (code "63") (name "Net-(U5-D)") (class "Default")
      (node (ref "LS1") (pin "N") (pinfunction "N_N") (pintype "passive"))
      (node (ref "U5") (pin "3") (pinfunction "D_3") (pintype "output"))
    )
    (net (code "64") (name "Net-(U5-G)") (class "Default")
      (node (ref "R18") (pin "2") (pinfunction "2_2") (pintype "passive"))
      (node (ref "R19") (pin "1") (pinfunction "1_1") (pintype "passive"))
      (node (ref "U5") (pin "1") (pinfunction "G_1") (pintype "power_in"))
    )
    (net (code "65") (name "unconnected-(AP2112K_3.3V-NC-Pad4)") (class "Default")
      (node (ref "AP2112K_3.3V") (pin "4") (pinfunction "NC_4") (pintype "no_connect"))
    )
    (net (code "66") (name "unconnected-(U1-A2_PB09(AIN3{slash}SER4:1{slash}TC4:1)-Pad8)") (class "Default")
      (node (ref "U1") (pin "8") (pinfunction "A2_PB09(AIN3/SER4:1/TC4:1)_8") (pintype "bidirectional"))
    )
    (net (code "67") (name "unconnected-(U4-ADC1-Pad16)") (class "Default")
      (node (ref "U4") (pin "16") (pinfunction "ADC1_16") (pintype "bidirectional"))
    )
    (net (code "68") (name "unconnected-(U4-ADC2-Pad15)") (class "Default")
      (node (ref "U4") (pin "15") (pinfunction "ADC2_15") (pintype "bidirectional"))
    )
    (net (code "69") (name "unconnected-(U4-ADC3-Pad13)") (class "Default")
      (node (ref "U4") (pin "13") (pinfunction "ADC3_13") (pintype "bidirectional"))
    )
    (net (code "70") (name "unconnected-(U4-INT1-Pad11)") (class "Default")
      (node (ref "U4") (pin "11") (pinfunction "INT1_11") (pintype "bidirectional"))
    )
  )
)
